# Encoder.net
KiCad netlist of a schematic drawn in EAGLE
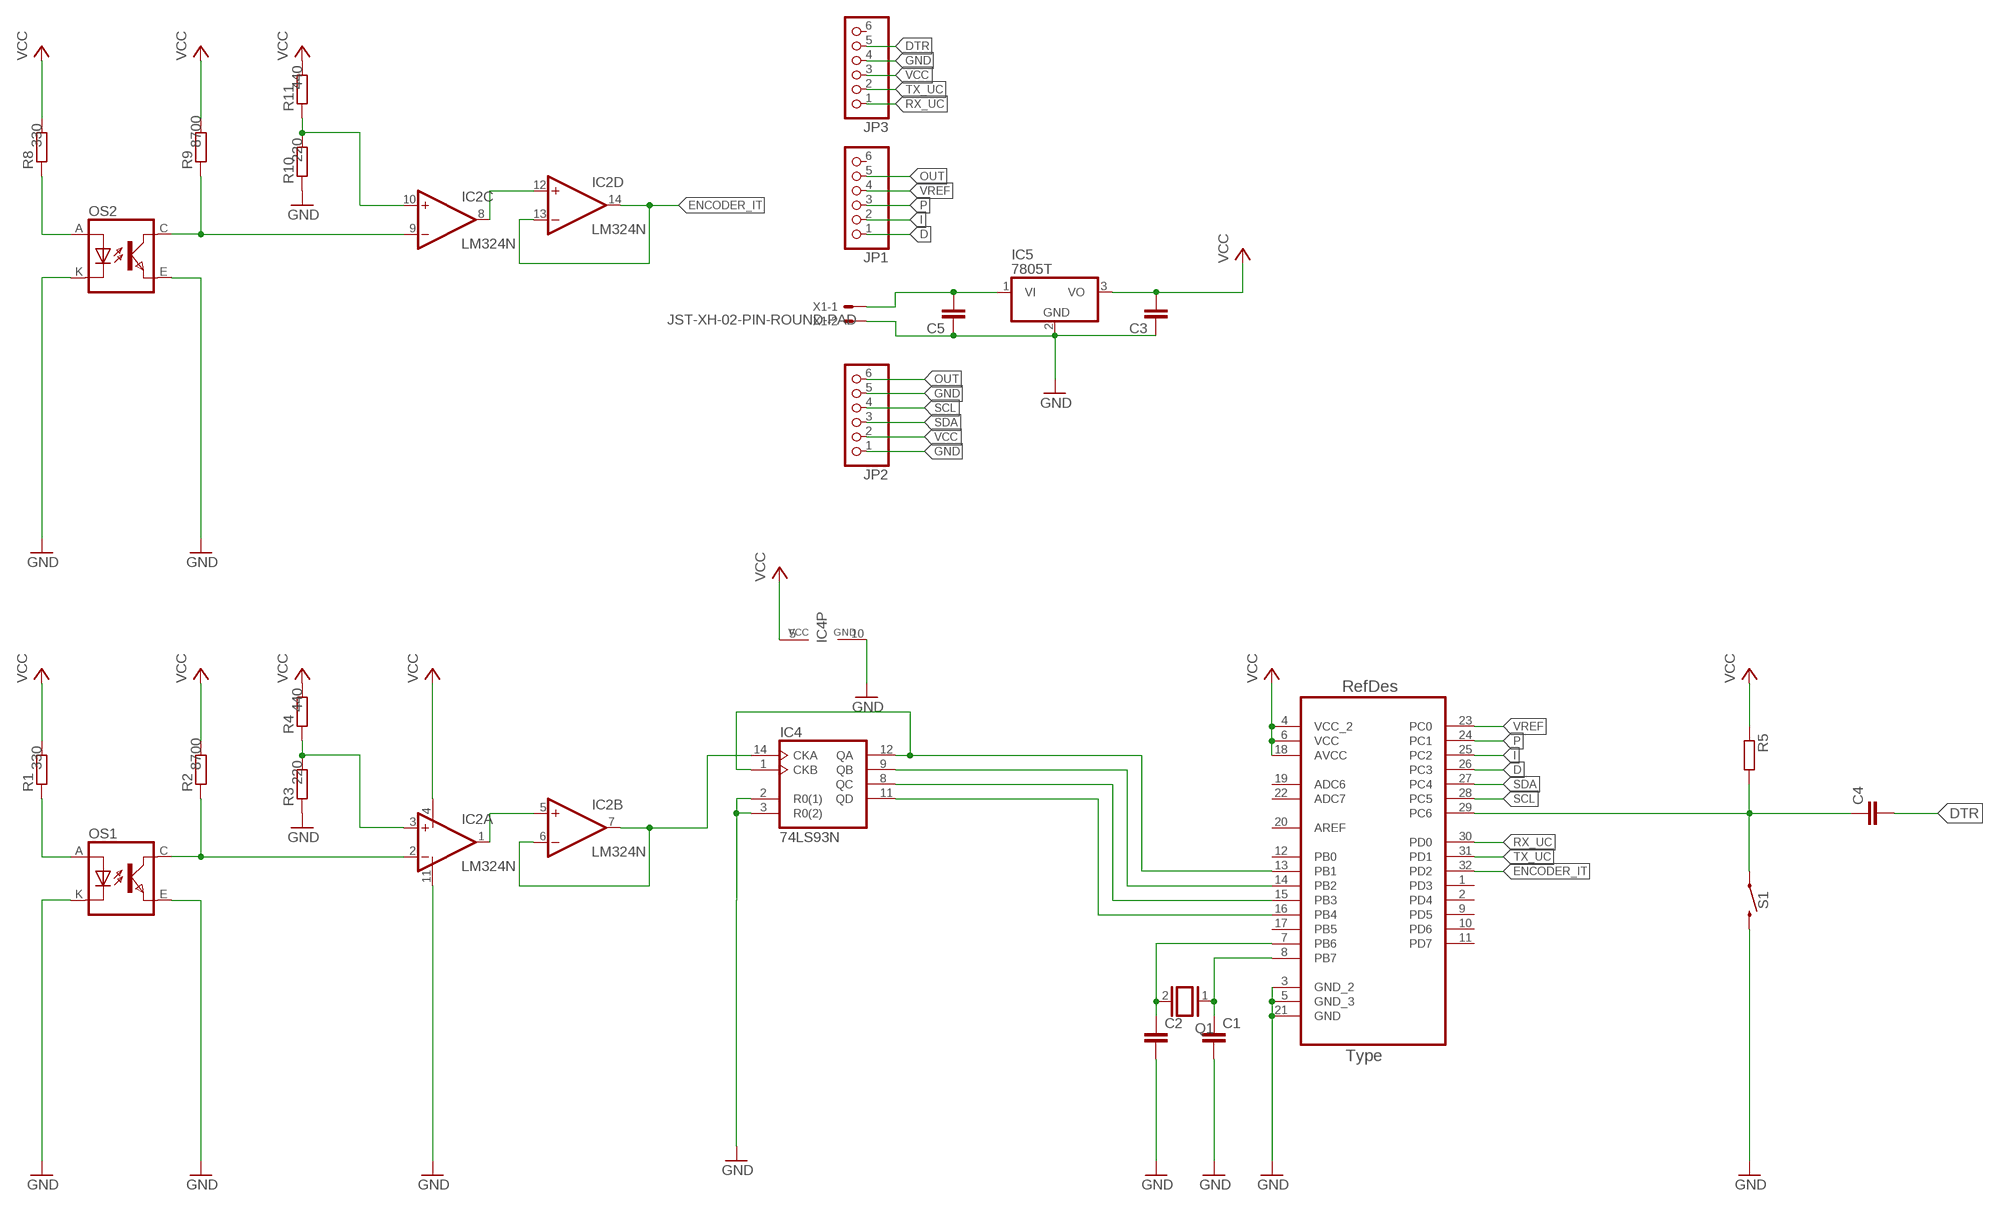
[diagram p0: schematic, sheet 1]

(export (version "E")
  (design (tool "Eeschema 10.0.6"))
  (components
    (comp (ref "C1")
      (value "C-EUC1206")
      (footprint "eagle-import:C1206")
      (libsource (lib "eagle-import") (part "C-EUC1206"))
    )
    (comp (ref "C2")
      (value "C-EUC1206")
      (footprint "eagle-import:C1206")
      (libsource (lib "eagle-import") (part "C-EUC1206"))
    )
    (comp (ref "C3")
      (value "C-EUC1206")
      (footprint "eagle-import:C1206")
      (libsource (lib "eagle-import") (part "C-EUC1206"))
    )
    (comp (ref "C4")
      (value "C-EUC1206")
      (footprint "eagle-import:C1206")
      (libsource (lib "eagle-import") (part "C-EUC1206"))
    )
    (comp (ref "C5")
      (value "C-EUC1206")
      (footprint "eagle-import:C1206")
      (libsource (lib "eagle-import") (part "C-EUC1206"))
    )
    (comp (ref "IC2")
      (value "LM324N")
      (footprint "eagle-import:DIL14")
      (libsource (lib "eagle-import") (part "LM324N"))
    )
    (comp (ref "IC4")
      (value "74LS93N")
      (footprint "eagle-import:DIL14")
      (libsource (lib "eagle-import") (part "7493NLS"))
    )
    (comp (ref "IC5")
      (value "7805T")
      (footprint "eagle-import:TO220H")
      (libsource (lib "eagle-import") (part "78T05"))
    )
    (comp (ref "JP1")
      (value "PINHD-1X6")
      (footprint "eagle-import:1X06")
      (libsource (lib "eagle-import") (part "PINHD-1X6"))
    )
    (comp (ref "JP2")
      (value "PINHD-1X6")
      (footprint "eagle-import:1X06")
      (libsource (lib "eagle-import") (part "PINHD-1X6"))
    )
    (comp (ref "JP3")
      (value "PINHD-1X6")
      (footprint "eagle-import:1X06")
      (libsource (lib "eagle-import") (part "PINHD-1X6"))
    )
    (comp (ref "OS1")
      (value "TCRT5000")
      (footprint "eagle-import:TCRT5000")
      (libsource (lib "eagle-import") (part "TCRT5000"))
    )
    (comp (ref "OS2")
      (value "TCRT5000")
      (footprint "eagle-import:TCRT5000")
      (libsource (lib "eagle-import") (part "TCRT5000"))
    )
    (comp (ref "Q1")
      (value "XTAL/S")
      (footprint "eagle-import:QS")
      (libsource (lib "eagle-import") (part "XTAL/S"))
    )
    (comp (ref "R1")
      (value "R-EU_M1206")
      (footprint "eagle-import:M1206")
      (fields (field (name "SPICEPREFIX") "R") (field (name "SPICEPREFIX_1") "330"))
      (libsource (lib "eagle-import") (part "R-EU_M1206"))
    )
    (comp (ref "R2")
      (value "R-EU_M1206")
      (footprint "eagle-import:M1206")
      (fields (field (name "SPICEPREFIX") "R") (field (name "SPICEPREFIX_1") "8700"))
      (libsource (lib "eagle-import") (part "R-EU_M1206"))
    )
    (comp (ref "R3")
      (value "R-EU_M1206")
      (footprint "eagle-import:M1206")
      (fields (field (name "SPICEPREFIX") "R") (field (name "SPICEPREFIX_1") "220"))
      (libsource (lib "eagle-import") (part "R-EU_M1206"))
    )
    (comp (ref "R4")
      (value "R-EU_M1206")
      (footprint "eagle-import:M1206")
      (fields (field (name "SPICEPREFIX") "R") (field (name "SPICEPREFIX_1") "440"))
      (libsource (lib "eagle-import") (part "R-EU_M1206"))
    )
    (comp (ref "R5")
      (value "R-EU_M1206")
      (footprint "eagle-import:M1206")
      (fields (field (name "SPICEPREFIX") "330"))
      (libsource (lib "eagle-import") (part "R-EU_M1206"))
    )
    (comp (ref "R8")
      (value "R-EU_M1206")
      (footprint "eagle-import:M1206")
      (fields (field (name "SPICEPREFIX") "R") (field (name "SPICEPREFIX_1") "330"))
      (libsource (lib "eagle-import") (part "R-EU_M1206"))
    )
    (comp (ref "R9")
      (value "R-EU_M1206")
      (footprint "eagle-import:M1206")
      (fields (field (name "SPICEPREFIX") "R") (field (name "SPICEPREFIX_1") "8700"))
      (libsource (lib "eagle-import") (part "R-EU_M1206"))
    )
    (comp (ref "R10")
      (value "R-EU_M1206")
      (footprint "eagle-import:M1206")
      (fields (field (name "SPICEPREFIX") "R") (field (name "SPICEPREFIX_1") "220"))
      (libsource (lib "eagle-import") (part "R-EU_M1206"))
    )
    (comp (ref "R11")
      (value "R-EU_M1206")
      (footprint "eagle-import:M1206")
      (fields (field (name "SPICEPREFIX") "R") (field (name "SPICEPREFIX_1") "440"))
      (libsource (lib "eagle-import") (part "R-EU_M1206"))
    )
    (comp (ref "S1")
      (value "MOMENTARY-SWITCH-SPST-PTH-6.0MM")
      (footprint "eagle-import:TACTILE_SWITCH_PTH_6.0MM")
      (libsource (lib "eagle-import") (part "MOMENTARY-SWITCH-SPST-PTH-6.0MM"))
    )
    (comp (ref "U1")
      (value "ATMEGA328P-AU")
      (footprint "eagle-import:QFP80P900X900X120-32N")
      (libsource (lib "eagle-import") (part "ATMEGA328P-AU"))
    )
    (comp (ref "X1")
      (value "JST-XH-02-PIN-ROUND-PAD")
      (footprint "eagle-import:JST-XH-02-PACKAGE-ROUND-PAD")
      (libsource (lib "eagle-import") (part "JST-XH-02-PIN-ROUND-PAD"))
    )
  )
  (nets
    (net (code "1") (name "D") (class "Default")
      (node (ref "JP1") (pin "1") (pinfunction "1_1") (pintype "passive"))
      (node (ref "U1") (pin "26") (pinfunction "PC3_26") (pintype "bidirectional"))
    )
    (net (code "2") (name "DTR") (class "Default")
      (node (ref "C4") (pin "2") (pinfunction "2_2") (pintype "passive"))
      (node (ref "JP3") (pin "5") (pinfunction "5_5") (pintype "passive"))
    )
    (net (code "3") (name "ENCODER_IT") (class "Default")
      (node (ref "IC2") (pin "13") (pinfunction "-IN_13") (pintype "input"))
      (node (ref "IC2") (pin "14") (pinfunction "OUT_14") (pintype "output"))
      (node (ref "U1") (pin "32") (pinfunction "PD2_32") (pintype "bidirectional"))
    )
    (net (code "4") (name "GND") (class "Default")
      (node (ref "C1") (pin "2") (pinfunction "2_2") (pintype "passive"))
      (node (ref "C2") (pin "2") (pinfunction "2_2") (pintype "passive"))
      (node (ref "C3") (pin "1") (pinfunction "1_1") (pintype "passive"))
      (node (ref "C5") (pin "1") (pinfunction "1_1") (pintype "passive"))
      (node (ref "IC2") (pin "11") (pinfunction "V-_11") (pintype "power_in"))
      (node (ref "IC4") (pin "10") (pinfunction "GND_10") (pintype "power_in"))
      (node (ref "IC4") (pin "2") (pinfunction "R0(1)_2") (pintype "input"))
      (node (ref "IC4") (pin "3") (pinfunction "R0(2)_3") (pintype "input"))
      (node (ref "IC5") (pin "2") (pinfunction "GND_2") (pintype "passive"))
      (node (ref "JP2") (pin "1") (pinfunction "1_1") (pintype "passive"))
      (node (ref "JP2") (pin "5") (pinfunction "5_5") (pintype "passive"))
      (node (ref "JP3") (pin "4") (pinfunction "4_4") (pintype "passive"))
      (node (ref "OS1") (pin "E") (pinfunction "EMITTER_E") (pintype "passive"))
      (node (ref "OS1") (pin "K") (pinfunction "CATHODE_K") (pintype "passive"))
      (node (ref "OS2") (pin "E") (pinfunction "EMITTER_E") (pintype "passive"))
      (node (ref "OS2") (pin "K") (pinfunction "CATHODE_K") (pintype "passive"))
      (node (ref "R10") (pin "1") (pinfunction "1_1") (pintype "passive"))
      (node (ref "R3") (pin "1") (pinfunction "1_1") (pintype "passive"))
      (node (ref "S1") (pin "3") (pinfunction "2_3") (pintype "passive"))
      (node (ref "U1") (pin "21") (pinfunction "GND_21") (pintype "passive"))
      (node (ref "U1") (pin "3") (pinfunction "GND_2_3") (pintype "passive"))
      (node (ref "U1") (pin "5") (pinfunction "GND_3_5") (pintype "passive"))
      (node (ref "X1") (pin "2") (pinfunction "S_2") (pintype "passive"))
    )
    (net (code "5") (name "I") (class "Default")
      (node (ref "JP1") (pin "2") (pinfunction "2_2") (pintype "passive"))
      (node (ref "U1") (pin "25") (pinfunction "PC2_25") (pintype "bidirectional"))
    )
    (net (code "6") (name "Net-(IC2A-+IN)") (class "Default")
      (node (ref "IC2") (pin "3") (pinfunction "+IN_3") (pintype "input"))
      (node (ref "R3") (pin "2") (pinfunction "2_2") (pintype "passive"))
      (node (ref "R4") (pin "1") (pinfunction "1_1") (pintype "passive"))
    )
    (net (code "7") (name "Net-(IC2A--IN)") (class "Default")
      (node (ref "IC2") (pin "2") (pinfunction "-IN_2") (pintype "input"))
      (node (ref "OS1") (pin "C") (pinfunction "COLLECTOR_C") (pintype "passive"))
      (node (ref "R2") (pin "1") (pinfunction "1_1") (pintype "passive"))
    )
    (net (code "8") (name "Net-(IC2A-OUT)") (class "Default")
      (node (ref "IC2") (pin "1") (pinfunction "OUT_1") (pintype "output"))
      (node (ref "IC2") (pin "5") (pinfunction "+IN_5") (pintype "input"))
    )
    (net (code "9") (name "Net-(IC2B--IN)") (class "Default")
      (node (ref "IC2") (pin "6") (pinfunction "-IN_6") (pintype "input"))
      (node (ref "IC2") (pin "7") (pinfunction "OUT_7") (pintype "output"))
      (node (ref "IC4") (pin "14") (pinfunction "CKA_14") (pintype "input"))
    )
    (net (code "10") (name "Net-(IC2C-+IN)") (class "Default")
      (node (ref "IC2") (pin "10") (pinfunction "+IN_10") (pintype "input"))
      (node (ref "R10") (pin "2") (pinfunction "2_2") (pintype "passive"))
      (node (ref "R11") (pin "1") (pinfunction "1_1") (pintype "passive"))
    )
    (net (code "11") (name "Net-(IC2C--IN)") (class "Default")
      (node (ref "IC2") (pin "9") (pinfunction "-IN_9") (pintype "input"))
      (node (ref "OS2") (pin "C") (pinfunction "COLLECTOR_C") (pintype "passive"))
      (node (ref "R9") (pin "1") (pinfunction "1_1") (pintype "passive"))
    )
    (net (code "12") (name "Net-(IC2C-OUT)") (class "Default")
      (node (ref "IC2") (pin "12") (pinfunction "+IN_12") (pintype "input"))
      (node (ref "IC2") (pin "8") (pinfunction "OUT_8") (pintype "output"))
    )
    (net (code "13") (name "Net-(IC4A-CKB)") (class "Default")
      (node (ref "IC4") (pin "1") (pinfunction "CKB_1") (pintype "input"))
      (node (ref "IC4") (pin "12") (pinfunction "QA_12") (pintype "output"))
      (node (ref "U1") (pin "13") (pinfunction "PB1_13") (pintype "bidirectional"))
    )
    (net (code "14") (name "Net-(IC4A-QB)") (class "Default")
      (node (ref "IC4") (pin "9") (pinfunction "QB_9") (pintype "output"))
      (node (ref "U1") (pin "14") (pinfunction "PB2_14") (pintype "bidirectional"))
    )
    (net (code "15") (name "Net-(IC4A-QC)") (class "Default")
      (node (ref "IC4") (pin "8") (pinfunction "QC_8") (pintype "output"))
      (node (ref "U1") (pin "15") (pinfunction "PB3_15") (pintype "bidirectional"))
    )
    (net (code "16") (name "Net-(IC4A-QD)") (class "Default")
      (node (ref "IC4") (pin "11") (pinfunction "QD_11") (pintype "output"))
      (node (ref "U1") (pin "16") (pinfunction "PB4_16") (pintype "bidirectional"))
    )
    (net (code "17") (name "Net-(IC5-VI)") (class "Default")
      (node (ref "C5") (pin "2") (pinfunction "2_2") (pintype "passive"))
      (node (ref "IC5") (pin "1") (pinfunction "VI_1") (pintype "input"))
      (node (ref "X1") (pin "1") (pinfunction "S_1") (pintype "passive"))
    )
    (net (code "18") (name "Net-(OS1-ANODE)") (class "Default")
      (node (ref "OS1") (pin "A") (pinfunction "ANODE_A") (pintype "passive"))
      (node (ref "R1") (pin "1") (pinfunction "1_1") (pintype "passive"))
    )
    (net (code "19") (name "Net-(OS2-ANODE)") (class "Default")
      (node (ref "OS2") (pin "A") (pinfunction "ANODE_A") (pintype "passive"))
      (node (ref "R8") (pin "1") (pinfunction "1_1") (pintype "passive"))
    )
    (net (code "20") (name "Net-(U1-PB6)") (class "Default")
      (node (ref "C2") (pin "1") (pinfunction "1_1") (pintype "passive"))
      (node (ref "Q1") (pin "2") (pinfunction "2_2") (pintype "passive"))
      (node (ref "U1") (pin "7") (pinfunction "PB6_7") (pintype "bidirectional"))
    )
    (net (code "21") (name "Net-(U1-PB7)") (class "Default")
      (node (ref "C1") (pin "1") (pinfunction "1_1") (pintype "passive"))
      (node (ref "Q1") (pin "1") (pinfunction "1_1") (pintype "passive"))
      (node (ref "U1") (pin "8") (pinfunction "PB7_8") (pintype "bidirectional"))
    )
    (net (code "22") (name "Net-(U1-PC6)") (class "Default")
      (node (ref "C4") (pin "1") (pinfunction "1_1") (pintype "passive"))
      (node (ref "R5") (pin "2") (pinfunction "2_2") (pintype "passive"))
      (node (ref "S1") (pin "1") (pinfunction "1_1") (pintype "passive"))
      (node (ref "U1") (pin "29") (pinfunction "PC6_29") (pintype "bidirectional"))
    )
    (net (code "23") (name "OUT") (class "Default")
      (node (ref "JP1") (pin "5") (pinfunction "5_5") (pintype "passive"))
      (node (ref "JP2") (pin "6") (pinfunction "6_6") (pintype "passive"))
    )
    (net (code "24") (name "P") (class "Default")
      (node (ref "JP1") (pin "3") (pinfunction "3_3") (pintype "passive"))
      (node (ref "U1") (pin "24") (pinfunction "PC1_24") (pintype "bidirectional"))
    )
    (net (code "25") (name "RX_UC") (class "Default")
      (node (ref "JP3") (pin "1") (pinfunction "1_1") (pintype "passive"))
      (node (ref "U1") (pin "30") (pinfunction "PD0_30") (pintype "bidirectional"))
    )
    (net (code "26") (name "SCL") (class "Default")
      (node (ref "JP2") (pin "4") (pinfunction "4_4") (pintype "passive"))
      (node (ref "U1") (pin "28") (pinfunction "PC5_28") (pintype "bidirectional"))
    )
    (net (code "27") (name "SDA") (class "Default")
      (node (ref "JP2") (pin "3") (pinfunction "3_3") (pintype "passive"))
      (node (ref "U1") (pin "27") (pinfunction "PC4_27") (pintype "bidirectional"))
    )
    (net (code "28") (name "TX_UC") (class "Default")
      (node (ref "JP3") (pin "2") (pinfunction "2_2") (pintype "passive"))
      (node (ref "U1") (pin "31") (pinfunction "PD1_31") (pintype "bidirectional"))
    )
    (net (code "29") (name "VCC") (class "Default")
      (node (ref "C3") (pin "2") (pinfunction "2_2") (pintype "passive"))
      (node (ref "IC2") (pin "4") (pinfunction "V+_4") (pintype "power_in"))
      (node (ref "IC4") (pin "5") (pinfunction "VCC_5") (pintype "power_in"))
      (node (ref "IC5") (pin "3") (pinfunction "VO_3") (pintype "passive"))
      (node (ref "JP2") (pin "2") (pinfunction "2_2") (pintype "passive"))
      (node (ref "JP3") (pin "3") (pinfunction "3_3") (pintype "passive"))
      (node (ref "R1") (pin "2") (pinfunction "2_2") (pintype "passive"))
      (node (ref "R11") (pin "2") (pinfunction "2_2") (pintype "passive"))
      (node (ref "R2") (pin "2") (pinfunction "2_2") (pintype "passive"))
      (node (ref "R4") (pin "2") (pinfunction "2_2") (pintype "passive"))
      (node (ref "R5") (pin "1") (pinfunction "1_1") (pintype "passive"))
      (node (ref "R8") (pin "2") (pinfunction "2_2") (pintype "passive"))
      (node (ref "R9") (pin "2") (pinfunction "2_2") (pintype "passive"))
      (node (ref "U1") (pin "18") (pinfunction "AVCC_18") (pintype "power_in"))
      (node (ref "U1") (pin "4") (pinfunction "VCC_2_4") (pintype "power_in"))
      (node (ref "U1") (pin "6") (pinfunction "VCC_6") (pintype "power_in"))
    )
    (net (code "30") (name "VREF") (class "Default")
      (node (ref "JP1") (pin "4") (pinfunction "4_4") (pintype "passive"))
      (node (ref "U1") (pin "23") (pinfunction "PC0_23") (pintype "bidirectional"))
    )
    (net (code "31") (name "unconnected-(JP1-Pad6)") (class "Default")
      (node (ref "JP1") (pin "6") (pinfunction "6_6") (pintype "passive"))
    )
    (net (code "32") (name "unconnected-(JP3-Pad6)") (class "Default")
      (node (ref "JP3") (pin "6") (pinfunction "6_6") (pintype "passive"))
    )
    (net (code "33") (name "unconnected-(U1-ADC6-Pad19)") (class "Default")
      (node (ref "U1") (pin "19") (pinfunction "ADC6_19") (pintype "input"))
    )
    (net (code "34") (name "unconnected-(U1-ADC7-Pad22)") (class "Default")
      (node (ref "U1") (pin "22") (pinfunction "ADC7_22") (pintype "input"))
    )
    (net (code "35") (name "unconnected-(U1-AREF-Pad20)") (class "Default")
      (node (ref "U1") (pin "20") (pinfunction "AREF_20") (pintype "input"))
    )
    (net (code "36") (name "unconnected-(U1-PB0-Pad12)") (class "Default")
      (node (ref "U1") (pin "12") (pinfunction "PB0_12") (pintype "bidirectional"))
    )
    (net (code "37") (name "unconnected-(U1-PB5-Pad17)") (class "Default")
      (node (ref "U1") (pin "17") (pinfunction "PB5_17") (pintype "bidirectional"))
    )
    (net (code "38") (name "unconnected-(U1-PD3-Pad1)") (class "Default")
      (node (ref "U1") (pin "1") (pinfunction "PD3_1") (pintype "bidirectional"))
    )
    (net (code "39") (name "unconnected-(U1-PD4-Pad2)") (class "Default")
      (node (ref "U1") (pin "2") (pinfunction "PD4_2") (pintype "bidirectional"))
    )
    (net (code "40") (name "unconnected-(U1-PD5-Pad9)") (class "Default")
      (node (ref "U1") (pin "9") (pinfunction "PD5_9") (pintype "bidirectional"))
    )
    (net (code "41") (name "unconnected-(U1-PD6-Pad10)") (class "Default")
      (node (ref "U1") (pin "10") (pinfunction "PD6_10") (pintype "bidirectional"))
    )
    (net (code "42") (name "unconnected-(U1-PD7-Pad11)") (class "Default")
      (node (ref "U1") (pin "11") (pinfunction "PD7_11") (pintype "bidirectional"))
    )
  )
)
